# PIC18-USB_ICSP-Board.net
KiCad netlist of a schematic drawn in EAGLE
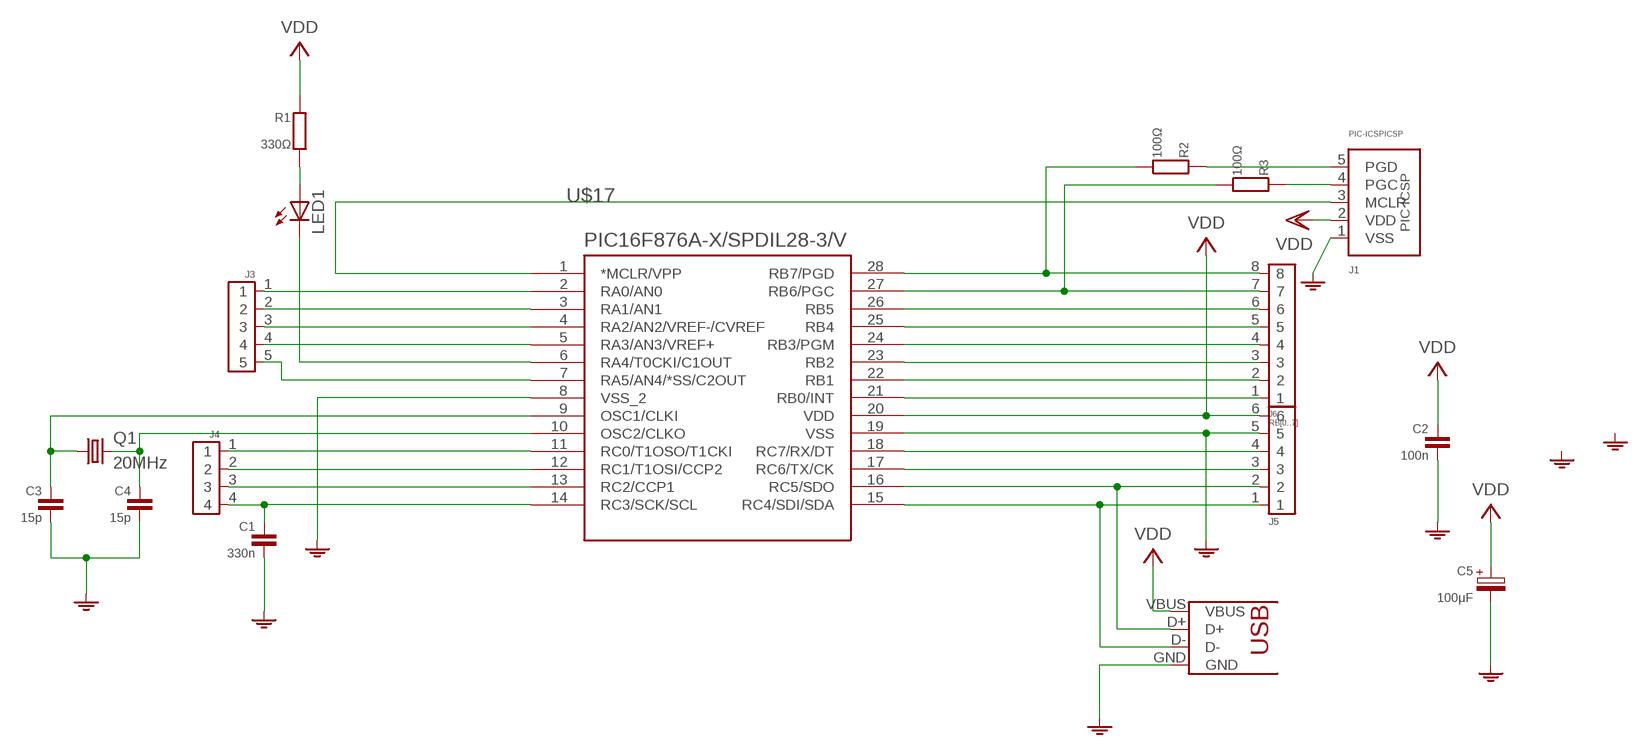
[diagram p0: schematic, sheet 1]

(export (version "E")
  (design (tool "Eeschema 10.0.6"))
  (components
    (comp (ref "C1")
      (value "330n")
      (footprint "eagle-import:C050-030X075")
      (libsource (lib "eagle-import") (part "C050-030X075"))
    )
    (comp (ref "C2")
      (value "100n")
      (footprint "eagle-import:C025-015X024")
      (libsource (lib "eagle-import") (part "C025-015X024"))
    )
    (comp (ref "C3")
      (value "15p")
      (footprint "eagle-import:C025-015X024")
      (libsource (lib "eagle-import") (part "C025-015X024"))
    )
    (comp (ref "C4")
      (value "15p")
      (footprint "eagle-import:C025-015X024")
      (libsource (lib "eagle-import") (part "C025-015X024"))
    )
    (comp (ref "C5")
      (value "100μF")
      (footprint "eagle-import:E2,5-5")
      (libsource (lib "eagle-import") (part "CPOLE2.5-5"))
    )
    (comp (ref "J1")
      (value "PIC-ICSPICSP")
      (footprint "eagle-import:PIC-ICSP")
      (libsource (lib "eagle-import") (part "PIC-ICSPICSP"))
    )
    (comp (ref "J2")
      (value "USB-PRINT")
      (footprint "eagle-import:USB-B-PRINT")
      (libsource (lib "eagle-import") (part "USB-PRINT"))
    )
    (comp (ref "J3")
      (value "RA[0..4]")
      (footprint "eagle-import:CONN-5P")
      (libsource (lib "eagle-import") (part "CONN-5P-5P"))
    )
    (comp (ref "J4")
      (value "RC[0..3]")
      (footprint "eagle-import:CONN-4P")
      (libsource (lib "eagle-import") (part "CONN-4P-4P"))
    )
    (comp (ref "J5")
      (value "PWR+SCI+USB")
      (footprint "eagle-import:CONN-6P")
      (libsource (lib "eagle-import") (part "CONN-6P"))
    )
    (comp (ref "J6")
      (value "RB[0..7]")
      (footprint "eagle-import:CONN-8P")
      (libsource (lib "eagle-import") (part "CONN-8P"))
    )
    (comp (ref "LED1")
      (value "LED5MM")
      (footprint "eagle-import:LED5MM")
      (libsource (lib "eagle-import") (part "LED5MM"))
    )
    (comp (ref "Q1")
      (value "20MHz")
      (footprint "eagle-import:HC49")
      (libsource (lib "eagle-import") (part "CRYSTALHC49"))
    )
    (comp (ref "R1")
      (value "330Ω")
      (footprint "eagle-import:0204_10")
      (libsource (lib "eagle-import") (part "R0204/10"))
    )
    (comp (ref "R2")
      (value "100Ω")
      (footprint "eagle-import:0204_7-V")
      (libsource (lib "eagle-import") (part "R0204/7-V"))
    )
    (comp (ref "R3")
      (value "100Ω")
      (footprint "eagle-import:0204_7-V")
      (libsource (lib "eagle-import") (part "R0204/7-V"))
    )
    (comp (ref "U$17")
      (value "PIC16F876A-X/SPDIL28-3/V")
      (footprint "eagle-import:DIL28-3_V")
      (libsource (lib "eagle-import") (part "PIC16F876A-X/SPDIL28-3/V"))
    )
  )
  (nets
    (net (code "1") (name "GND") (class "Default")
      (node (ref "C1") (pin "2") (pinfunction "2_2") (pintype "passive"))
      (node (ref "C2") (pin "2") (pinfunction "2_2") (pintype "passive"))
      (node (ref "C3") (pin "2") (pinfunction "2_2") (pintype "passive"))
      (node (ref "C4") (pin "2") (pinfunction "2_2") (pintype "passive"))
      (node (ref "C5") (pin "-") (pinfunction "-_-") (pintype "passive"))
      (node (ref "J1") (pin "1") (pinfunction "VSS_1") (pintype "passive"))
      (node (ref "J2") (pin "GND") (pinfunction "GND_GND") (pintype "bidirectional"))
      (node (ref "J5") (pin "5") (pinfunction "5_5") (pintype "bidirectional"))
      (node (ref "U$17") (pin "19") (pinfunction "VSS_19") (pintype "passive"))
      (node (ref "U$17") (pin "8") (pinfunction "VSS_2_8") (pintype "passive"))
    )
    (net (code "2") (name "Net-(J1-MCLR)") (class "Default")
      (node (ref "J1") (pin "3") (pinfunction "MCLR_3") (pintype "passive"))
      (node (ref "U$17") (pin "1") (pinfunction "*MCLR/VPP_1") (pintype "passive"))
    )
    (net (code "3") (name "Net-(J1-PGC)") (class "Default")
      (node (ref "J1") (pin "4") (pinfunction "PGC_4") (pintype "passive"))
      (node (ref "R3") (pin "1") (pinfunction "2_1") (pintype "passive"))
    )
    (net (code "4") (name "Net-(J1-PGD)") (class "Default")
      (node (ref "J1") (pin "5") (pinfunction "PGD_5") (pintype "passive"))
      (node (ref "R2") (pin "1") (pinfunction "2_1") (pintype "passive"))
    )
    (net (code "5") (name "Net-(LED1-C)") (class "Default")
      (node (ref "LED1") (pin "K") (pinfunction "C_K") (pintype "passive"))
      (node (ref "U$17") (pin "6") (pinfunction "RA4/T0CKI/C1OUT_6") (pintype "passive"))
    )
    (net (code "6") (name "Net-(R1-1)") (class "Default")
      (node (ref "LED1") (pin "A") (pinfunction "A_A") (pintype "passive"))
      (node (ref "R1") (pin "2") (pinfunction "1_2") (pintype "passive"))
    )
    (net (code "7") (name "Net-(R2-1)") (class "Default")
      (node (ref "J6") (pin "8") (pinfunction "8_8") (pintype "passive"))
      (node (ref "R2") (pin "2") (pinfunction "1_2") (pintype "passive"))
      (node (ref "U$17") (pin "28") (pinfunction "RB7/PGD_28") (pintype "passive"))
    )
    (net (code "8") (name "Net-(R3-1)") (class "Default")
      (node (ref "J6") (pin "7") (pinfunction "7_7") (pintype "passive"))
      (node (ref "R3") (pin "2") (pinfunction "1_2") (pintype "passive"))
      (node (ref "U$17") (pin "27") (pinfunction "RB6/PGC_27") (pintype "passive"))
    )
    (net (code "9") (name "Net-(U$17-OSC1{slash}CLKI)") (class "Default")
      (node (ref "C3") (pin "1") (pinfunction "1_1") (pintype "passive"))
      (node (ref "Q1") (pin "1") (pinfunction "1_1") (pintype "passive"))
      (node (ref "U$17") (pin "9") (pinfunction "OSC1/CLKI_9") (pintype "passive"))
    )
    (net (code "10") (name "Net-(U$17-OSC2{slash}CLKO)") (class "Default")
      (node (ref "C4") (pin "1") (pinfunction "1_1") (pintype "passive"))
      (node (ref "Q1") (pin "2") (pinfunction "2_2") (pintype "passive"))
      (node (ref "U$17") (pin "10") (pinfunction "OSC2/CLKO_10") (pintype "passive"))
    )
    (net (code "11") (name "Net-(U$17-RA0{slash}AN0)") (class "Default")
      (node (ref "J3") (pin "1") (pinfunction "1_1") (pintype "bidirectional"))
      (node (ref "U$17") (pin "2") (pinfunction "RA0/AN0_2") (pintype "passive"))
    )
    (net (code "12") (name "Net-(U$17-RA1{slash}AN1)") (class "Default")
      (node (ref "J3") (pin "2") (pinfunction "2_2") (pintype "bidirectional"))
      (node (ref "U$17") (pin "3") (pinfunction "RA1/AN1_3") (pintype "passive"))
    )
    (net (code "13") (name "Net-(U$17-RA2{slash}AN2{slash}VREF-{slash}CVREF)") (class "Default")
      (node (ref "J3") (pin "3") (pinfunction "3_3") (pintype "bidirectional"))
      (node (ref "U$17") (pin "4") (pinfunction "RA2/AN2/VREF-/CVREF_4") (pintype "passive"))
    )
    (net (code "14") (name "Net-(U$17-RA3{slash}AN3{slash}VREF+)") (class "Default")
      (node (ref "J3") (pin "4") (pinfunction "4_4") (pintype "bidirectional"))
      (node (ref "U$17") (pin "5") (pinfunction "RA3/AN3/VREF+_5") (pintype "passive"))
    )
    (net (code "15") (name "Net-(U$17-RA5{slash}AN4{slash}*SS{slash}C2OUT)") (class "Default")
      (node (ref "J3") (pin "5") (pinfunction "5_5") (pintype "bidirectional"))
      (node (ref "U$17") (pin "7") (pinfunction "RA5/AN4/*SS/C2OUT_7") (pintype "passive"))
    )
    (net (code "16") (name "Net-(U$17-RB0{slash}INT)") (class "Default")
      (node (ref "J6") (pin "1") (pinfunction "1_1") (pintype "passive"))
      (node (ref "U$17") (pin "21") (pinfunction "RB0/INT_21") (pintype "passive"))
    )
    (net (code "17") (name "Net-(U$17-RB1)") (class "Default")
      (node (ref "J6") (pin "2") (pinfunction "2_2") (pintype "passive"))
      (node (ref "U$17") (pin "22") (pinfunction "RB1_22") (pintype "passive"))
    )
    (net (code "18") (name "Net-(U$17-RB2)") (class "Default")
      (node (ref "J6") (pin "3") (pinfunction "3_3") (pintype "passive"))
      (node (ref "U$17") (pin "23") (pinfunction "RB2_23") (pintype "passive"))
    )
    (net (code "19") (name "Net-(U$17-RB3{slash}PGM)") (class "Default")
      (node (ref "J6") (pin "4") (pinfunction "4_4") (pintype "passive"))
      (node (ref "U$17") (pin "24") (pinfunction "RB3/PGM_24") (pintype "passive"))
    )
    (net (code "20") (name "Net-(U$17-RB4)") (class "Default")
      (node (ref "J6") (pin "5") (pinfunction "5_5") (pintype "passive"))
      (node (ref "U$17") (pin "25") (pinfunction "RB4_25") (pintype "passive"))
    )
    (net (code "21") (name "Net-(U$17-RB5)") (class "Default")
      (node (ref "J6") (pin "6") (pinfunction "6_6") (pintype "passive"))
      (node (ref "U$17") (pin "26") (pinfunction "RB5_26") (pintype "passive"))
    )
    (net (code "22") (name "Net-(U$17-RC0{slash}T1OSO{slash}T1CKI)") (class "Default")
      (node (ref "J4") (pin "1") (pinfunction "1_1") (pintype "bidirectional"))
      (node (ref "U$17") (pin "11") (pinfunction "RC0/T1OSO/T1CKI_11") (pintype "passive"))
    )
    (net (code "23") (name "Net-(U$17-RC1{slash}T1OSI{slash}CCP2)") (class "Default")
      (node (ref "J4") (pin "2") (pinfunction "2_2") (pintype "bidirectional"))
      (node (ref "U$17") (pin "12") (pinfunction "RC1/T1OSI/CCP2_12") (pintype "passive"))
    )
    (net (code "24") (name "Net-(U$17-RC2{slash}CCP1)") (class "Default")
      (node (ref "J4") (pin "3") (pinfunction "3_3") (pintype "bidirectional"))
      (node (ref "U$17") (pin "13") (pinfunction "RC2/CCP1_13") (pintype "passive"))
    )
    (net (code "25") (name "Net-(U$17-RC3{slash}SCK{slash}SCL)") (class "Default")
      (node (ref "C1") (pin "1") (pinfunction "1_1") (pintype "passive"))
      (node (ref "J4") (pin "4") (pinfunction "4_4") (pintype "bidirectional"))
      (node (ref "U$17") (pin "14") (pinfunction "RC3/SCK/SCL_14") (pintype "passive"))
    )
    (net (code "26") (name "Net-(U$17-RC4{slash}SDI{slash}SDA)") (class "Default")
      (node (ref "J2") (pin "D-") (pinfunction "D-_D-") (pintype "bidirectional"))
      (node (ref "J5") (pin "1") (pinfunction "1_1") (pintype "bidirectional"))
      (node (ref "U$17") (pin "15") (pinfunction "RC4/SDI/SDA_15") (pintype "passive"))
    )
    (net (code "27") (name "Net-(U$17-RC5{slash}SDO)") (class "Default")
      (node (ref "J2") (pin "D+") (pinfunction "D+_D+") (pintype "bidirectional"))
      (node (ref "J5") (pin "2") (pinfunction "2_2") (pintype "bidirectional"))
      (node (ref "U$17") (pin "16") (pinfunction "RC5/SDO_16") (pintype "passive"))
    )
    (net (code "28") (name "Net-(U$17-RC6{slash}TX{slash}CK)") (class "Default")
      (node (ref "J5") (pin "3") (pinfunction "3_3") (pintype "bidirectional"))
      (node (ref "U$17") (pin "17") (pinfunction "RC6/TX/CK_17") (pintype "passive"))
    )
    (net (code "29") (name "Net-(U$17-RC7{slash}RX{slash}DT)") (class "Default")
      (node (ref "J5") (pin "4") (pinfunction "4_4") (pintype "bidirectional"))
      (node (ref "U$17") (pin "18") (pinfunction "RC7/RX/DT_18") (pintype "passive"))
    )
    (net (code "30") (name "VDD") (class "Default")
      (node (ref "C2") (pin "1") (pinfunction "1_1") (pintype "passive"))
      (node (ref "C5") (pin "+") (pinfunction "+_+") (pintype "passive"))
      (node (ref "J1") (pin "2") (pinfunction "VDD_2") (pintype "passive"))
      (node (ref "J2") (pin "VBUS") (pinfunction "VBUS_VBUS") (pintype "bidirectional"))
      (node (ref "J5") (pin "6") (pinfunction "6_6") (pintype "bidirectional"))
      (node (ref "R1") (pin "1") (pinfunction "2_1") (pintype "passive"))
      (node (ref "U$17") (pin "20") (pinfunction "VDD_20") (pintype "passive"))
    )
  )
)
